# OPLink_Mini.net
KiCad netlist of a schematic drawn in Altium Designer
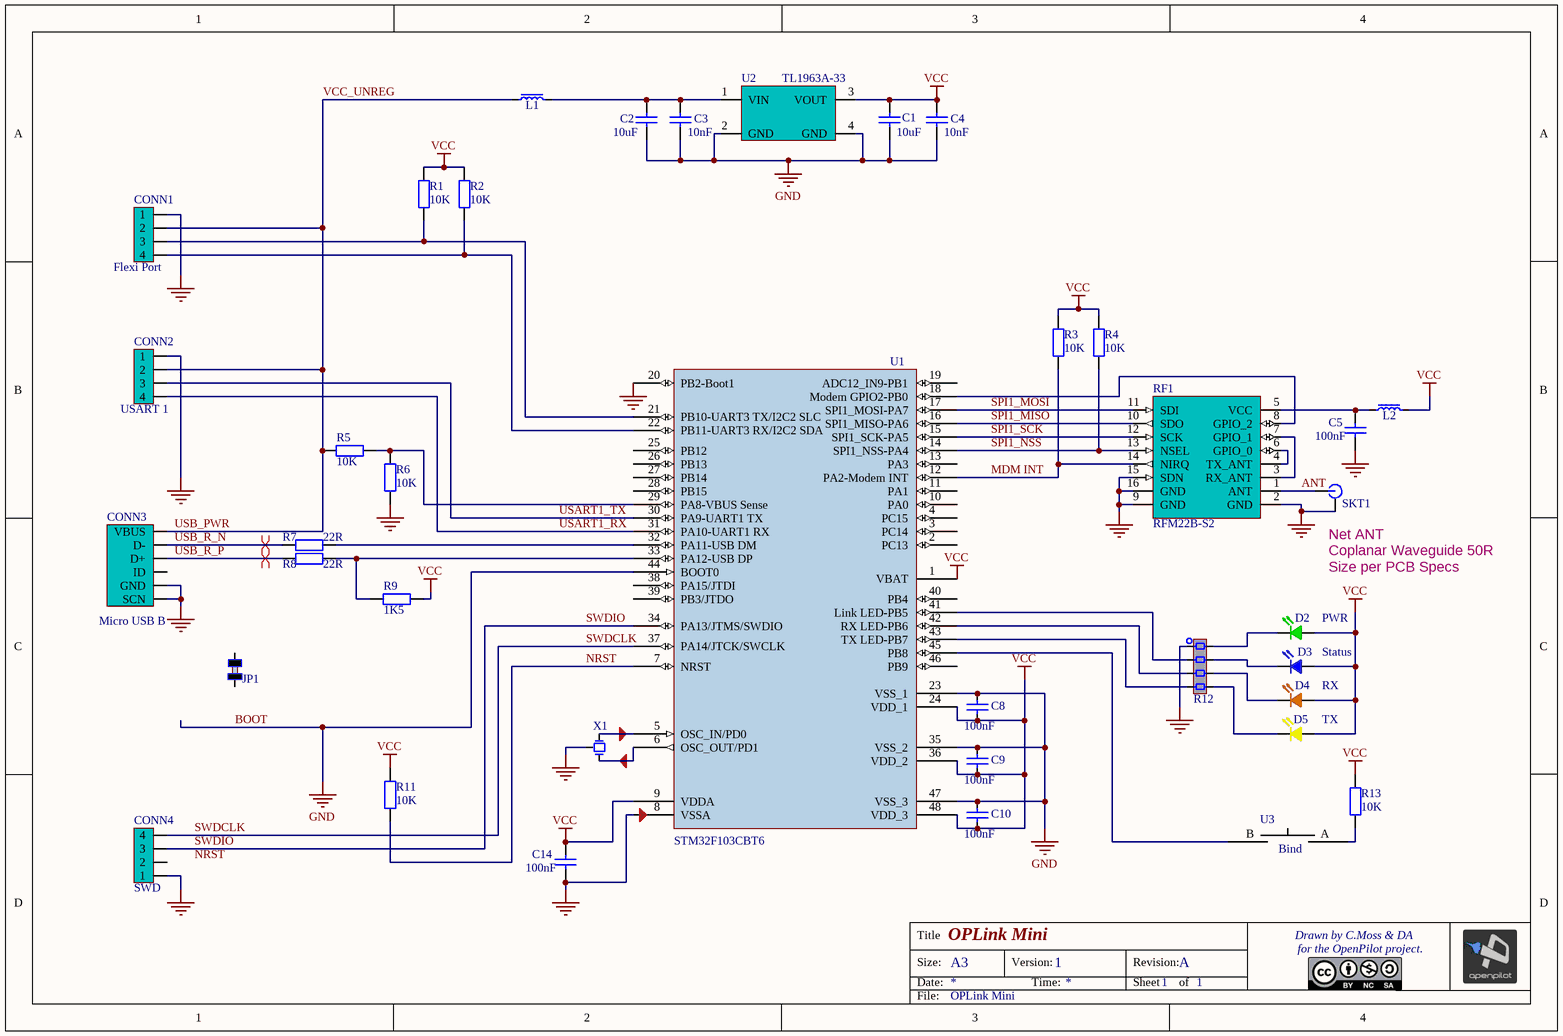
[diagram p0: OPLink Mini.SchDoc]

(export (version "E")
  (design (tool "Eeschema 10.0.6"))
  (components
    (comp (ref "C1")
      (value "10uF")
      (footprint "CAP805L")
      (description "Capacitor SMD")
      (fields (field (name "Comment") "Cap805") (field (name "PUBLISHER") "The OpenPilot Project"))
      (libsource (lib "OpenPilot") (part "Cap805"))
    )
    (comp (ref "C2")
      (value "10uF")
      (footprint "CAP805L")
      (description "Capacitor SMD")
      (fields (field (name "Comment") "Cap805") (field (name "PUBLISHER") "The OpenPilot Project"))
      (libsource (lib "OpenPilot") (part "Cap805"))
    )
    (comp (ref "C3")
      (value "10nF")
      (footprint "CAP402N")
      (description "Capacitor SMD")
      (fields (field (name "Comment") "10n") (field (name "PUBLISHER") "The OpenPilot Project"))
      (libsource (lib "OpenPilot") (part "Cap402"))
    )
    (comp (ref "C4")
      (value "10nF")
      (footprint "CAP402N")
      (description "Capacitor SMD")
      (fields (field (name "Comment") "10n") (field (name "PUBLISHER") "The OpenPilot Project"))
      (libsource (lib "OpenPilot") (part "Cap402"))
    )
    (comp (ref "C5")
      (value "100nF")
      (footprint "CAP402N")
      (description "Capacitor SMD")
      (fields (field (name "Comment") "Cap402") (field (name "PUBLISHER") "The OpenPilot Project"))
      (libsource (lib "OpenPilot") (part "Cap402"))
    )
    (comp (ref "C8")
      (value "100nF")
      (footprint "CAP402N")
      (description "Capacitor SMD")
      (fields (field (name "Comment") "Cap402") (field (name "PUBLISHER") "The OpenPilot Project"))
      (libsource (lib "") (part "Cap402_1"))
    )
    (comp (ref "C9")
      (value "100nF")
      (footprint "CAP402N")
      (description "Capacitor SMD")
      (fields (field (name "Comment") "Cap402") (field (name "PUBLISHER") "The OpenPilot Project"))
      (libsource (lib "") (part "Cap402_1"))
    )
    (comp (ref "C10")
      (value "100nF")
      (footprint "CAP402N")
      (description "Capacitor SMD")
      (fields (field (name "Comment") "Cap402") (field (name "PUBLISHER") "The OpenPilot Project"))
      (libsource (lib "") (part "Cap402_1"))
    )
    (comp (ref "C14")
      (value "100nF")
      (footprint "CAP402N")
      (description "Capacitor SMD")
      (fields (field (name "Comment") "Cap402") (field (name "PUBLISHER") "The OpenPilot Project"))
      (libsource (lib "OpenPilot") (part "Cap402"))
    )
    (comp (ref "CONN1")
      (value "Flexi Port")
      (footprint "JST SH 4 Pin Side Entry")
      (description "JST-SH 4-pin Side Entry Socket")
      (fields (field (name "MANUFACTURER") "Generic Components"))
      (libsource (lib "OpenPilot") (part "JST-SH 4-pin Side Entry Socket"))
    )
    (comp (ref "CONN2")
      (value "USART 1")
      (footprint "JST SH 4 Pin Side Entry")
      (description "JST-SH 4-pin Side Entry Socket")
      (fields (field (name "MANUFACTURER") "Generic Components"))
      (libsource (lib "OpenPilot") (part "JST-SH 4-pin Side Entry Socket"))
    )
    (comp (ref "CONN3")
      (value "Micro USB B")
      (footprint "Micro_USB")
      (description "USB Micro B SMT Socket")
      (fields (field (name "PUBLISHER") "The OpenPilot Project"))
      (libsource (lib "OpenPilot") (part "USB Micro B SMT"))
    )
    (comp (ref "CONN4")
      (value "SWD")
      (footprint "JST SH 4 Pin Side Entry")
      (description "JST-SH 4-pin Side Entry Socket")
      (fields (field (name "MANUFACTURER") "Generic Components"))
      (libsource (lib "") (part "JST-SH 4-pin Side Entry Socket_1"))
    )
    (comp (ref "D2")
      (value "PWR")
      (footprint "LED603N")
      (description "Green 603 LED")
      (libsource (lib "OpenPilot") (part "LED 603 Gr"))
    )
    (comp (ref "D3")
      (value "Status")
      (footprint "LED603N")
      (description "Blue 603 LED")
      (libsource (lib "OpenPilot") (part "LED 603 Bl"))
    )
    (comp (ref "D4")
      (value "RX")
      (footprint "LED603N")
      (description "Orange 603 LED")
      (libsource (lib "OpenPilot") (part "LED 603 Or"))
    )
    (comp (ref "D5")
      (value "TX")
      (footprint "LED603N")
      (description "Yellow 603 LED")
      (fields (field (name "PUBLISHER") "The OpenPilot Project"))
      (libsource (lib "OpenPilot") (part "LED 603 Yellow"))
    )
    (comp (ref "JP1")
      (value "2 PAD Touch JMP")
      (footprint "TOUCH JMP 2PAD")
      (description "2 Pad Touch Jumper")
      (fields (field (name "PUBLISHER") "The OpenPilot Project"))
      (libsource (lib "OpenPilot") (part "2 PAD Touch JMP"))
    )
    (comp (ref "L1")
      (value "300mA")
      (footprint "IND603N")
      (description "Ferrite Bead 300mA")
      (fields (field (name "MANUFACTURER") "Generic Components"))
      (libsource (lib "OpenPilot") (part "FerriteBead_300mA"))
    )
    (comp (ref "L2")
      (value "300mA")
      (footprint "IND603N")
      (description "Ferrite Bead 300mA")
      (fields (field (name "MANUFACTURER") "Generic Components"))
      (libsource (lib "OpenPilot") (part "FerriteBead_300mA"))
    )
    (comp (ref "R1")
      (value "10K")
      (footprint "RES402N")
      (description "Resistor SMD")
      (fields (field (name "Comment") "Res402") (field (name "PUBLISHER") "The OpenPilot Project"))
      (libsource (lib "") (part "Res402_2"))
    )
    (comp (ref "R2")
      (value "10K")
      (footprint "RES402N")
      (description "Resistor SMD")
      (fields (field (name "Comment") "Res402") (field (name "PUBLISHER") "The OpenPilot Project"))
      (libsource (lib "") (part "Res402_2"))
    )
    (comp (ref "R3")
      (value "10K")
      (footprint "RES402N")
      (description "Resistor SMD")
      (fields (field (name "Comment") "Res402") (field (name "PUBLISHER") "The OpenPilot Project"))
      (libsource (lib "") (part "Res402_2"))
    )
    (comp (ref "R4")
      (value "10K")
      (footprint "RES402N")
      (description "Resistor SMD")
      (fields (field (name "Comment") "Res402") (field (name "PUBLISHER") "The OpenPilot Project"))
      (libsource (lib "") (part "Res402_2"))
    )
    (comp (ref "R5")
      (value "10K")
      (footprint "RES402N")
      (description "Resistor SMD")
      (fields (field (name "Comment") "Res402") (field (name "PUBLISHER") "The OpenPilot Project"))
      (libsource (lib "") (part "Res402_1"))
    )
    (comp (ref "R6")
      (value "10K")
      (footprint "RES402N")
      (description "Resistor SMD")
      (fields (field (name "Comment") "Res402") (field (name "PUBLISHER") "The OpenPilot Project"))
      (libsource (lib "") (part "Res402_2"))
    )
    (comp (ref "R7")
      (value "22R")
      (footprint "RES402N")
      (description "Resistor SMD")
      (fields (field (name "Comment") "Res402") (field (name "PUBLISHER") "The OpenPilot Project"))
      (libsource (lib "") (part "Res402_1"))
    )
    (comp (ref "R8")
      (value "22R")
      (footprint "RES402N")
      (description "Resistor SMD")
      (fields (field (name "Comment") "Res402") (field (name "PUBLISHER") "The OpenPilot Project"))
      (libsource (lib "") (part "Res402_1"))
    )
    (comp (ref "R9")
      (value "1K5")
      (footprint "RES402N")
      (description "Resistor SMD")
      (fields (field (name "Comment") "Res402") (field (name "PUBLISHER") "The OpenPilot Project"))
      (libsource (lib "") (part "Res402_3"))
    )
    (comp (ref "R11")
      (value "10K")
      (footprint "RES402N")
      (description "Resistor SMD")
      (fields (field (name "Comment") "Res402") (field (name "PUBLISHER") "The OpenPilot Project"))
      (libsource (lib "OpenPilot") (part "Res402"))
    )
    (comp (ref "R12")
      (value "Res Array 330R 1206")
      (footprint "TC164")
      (description "4 Resistor Array")
      (fields (field (name "PUBLISHER") "The OpenPilot Project"))
      (libsource (lib "OpenPilot") (part "Res Array 330R"))
    )
    (comp (ref "R13")
      (value "10K")
      (footprint "RES402N")
      (description "Resistor SMD")
      (fields (field (name "Comment") "Res402") (field (name "PUBLISHER") "The OpenPilot Project"))
      (libsource (lib "OpenPilot") (part "Res402"))
    )
    (comp (ref "RF1")
      (value "RFM22B-S2")
      (footprint "RFM22-S2")
      (description "UHF 100mW Transceiver")
      (libsource (lib "OpenPilot") (part "RFM22B-S2"))
    )
    (comp (ref "SKT1")
      (value "MMCX Thru hole")
      (footprint "MMCX_SOCKET")
      (description "MMCX Socket")
      (libsource (lib "OpenPilot") (part "MMCX Thru hole"))
    )
    (comp (ref "U1")
      (value "STM32F103CBT6")
      (footprint "STM32 48 Lead")
      (description "STM32 ARM-based 32-bit MCU with 128 Kbytes Flash, 48-pin LQFP, Industrial Temperature")
      (fields (field (name "PUBLISHER") "Altium Limited"))
      (libsource (lib "OpenPilot") (part "STM32F103CBT6"))
    )
    (comp (ref "U2")
      (value "TL1963A-33")
      (footprint "SOT223")
      (description "3.3V 1.5A LDO Regulator")
      (fields (field (name "PUBLISHER") "The OpenPilot Project"))
      (libsource (lib "OpenPilot") (part "TL1963A-33"))
    )
    (comp (ref "U3")
      (value "Bind")
      (footprint "B3U-1000P")
      (description "Push Button SMD")
      (libsource (lib "OpenPilot") (part "Push Switch Small"))
    )
    (comp (ref "X1")
      (value "8Mhz Ceralock")
      (footprint "CERALOCK 8Mhz")
      (description "Ceralock 8Mhz with caps")
      (fields (field (name "PUBLISHER") "The OpenPilot Project"))
      (libsource (lib "OpenPilot") (part "CERALOCK8"))
    )
  )
  (nets
    (net (code "1") (name "/ANT") (class "Default")
      (node (ref "RF1") (pin "1") (pinfunction "ANT_1") (pintype "passive"))
      (node (ref "SKT1") (pin "1") (pinfunction "PIN_1") (pintype "passive"))
    )
    (net (code "2") (name "/MDM INT") (class "Default")
      (node (ref "R3") (pin "2") (pinfunction "2_2") (pintype "passive"))
      (node (ref "RF1") (pin "14") (pinfunction "NIRQ_14") (pintype "output"))
      (node (ref "U1") (pin "12") (pinfunction "PA2-Modem_INT_12") (pintype "bidirectional"))
    )
    (net (code "3") (name "/NRST") (class "Default")
      (node (ref "R11") (pin "1") (pinfunction "1_1") (pintype "passive"))
      (node (ref "U1") (pin "7") (pinfunction "NRST_7") (pintype "bidirectional"))
    )
    (net (code "4") (name "/SPI1_MISO") (class "Default")
      (node (ref "RF1") (pin "10") (pinfunction "SDO_10") (pintype "output"))
      (node (ref "U1") (pin "16") (pinfunction "SPI1_MISO-PA6_16") (pintype "bidirectional"))
    )
    (net (code "5") (name "/SPI1_MOSI") (class "Default")
      (node (ref "RF1") (pin "11") (pinfunction "SDI_11") (pintype "input"))
      (node (ref "U1") (pin "17") (pinfunction "SPI1_MOSI-PA7_17") (pintype "bidirectional"))
    )
    (net (code "6") (name "/SPI1_NSS") (class "Default")
      (node (ref "R4") (pin "2") (pinfunction "2_2") (pintype "passive"))
      (node (ref "RF1") (pin "13") (pinfunction "NSEL_13") (pintype "input"))
      (node (ref "U1") (pin "14") (pinfunction "SPI1_NSS-PA4_14") (pintype "bidirectional"))
    )
    (net (code "7") (name "/SPI1_SCK") (class "Default")
      (node (ref "RF1") (pin "12") (pinfunction "SCK_12") (pintype "input"))
      (node (ref "U1") (pin "15") (pinfunction "SPI1_SCK-PA5_15") (pintype "bidirectional"))
    )
    (net (code "8") (name "/SWDCLK") (class "Default")
      (node (ref "CONN4") (pin "4") (pinfunction "4_4") (pintype "passive"))
      (node (ref "U1") (pin "37") (pinfunction "PA14/JTCK/SWCLK_37") (pintype "bidirectional"))
    )
    (net (code "9") (name "/SWDIO") (class "Default")
      (node (ref "CONN4") (pin "3") (pinfunction "3_3") (pintype "passive"))
      (node (ref "U1") (pin "34") (pinfunction "PA13/JTMS/SWDIO_34") (pintype "bidirectional"))
    )
    (net (code "10") (name "/USART1_RX") (class "Default")
      (node (ref "CONN2") (pin "4") (pinfunction "4_4") (pintype "passive"))
      (node (ref "U1") (pin "31") (pinfunction "PA10-UART1_RX_31") (pintype "bidirectional"))
    )
    (net (code "11") (name "/USART1_TX") (class "Default")
      (node (ref "CONN2") (pin "3") (pinfunction "3_3") (pintype "passive"))
      (node (ref "U1") (pin "30") (pinfunction "PA9-UART1_TX_30") (pintype "bidirectional"))
    )
    (net (code "12") (name "/USB_PWR") (class "Default")
      (node (ref "CONN1") (pin "2") (pinfunction "2_2") (pintype "passive"))
      (node (ref "CONN2") (pin "2") (pinfunction "2_2") (pintype "passive"))
      (node (ref "CONN3") (pin "1") (pinfunction "VBUS_1") (pintype "passive"))
      (node (ref "L1") (pin "2") (pinfunction "2_2") (pintype "passive"))
      (node (ref "R5") (pin "2") (pinfunction "2_2") (pintype "passive"))
    )
    (net (code "13") (name "/USB_R_N") (class "Default")
      (node (ref "CONN3") (pin "2") (pinfunction "D-_2") (pintype "passive"))
      (node (ref "R7") (pin "2") (pinfunction "2_2") (pintype "passive"))
    )
    (net (code "14") (name "/USB_R_P") (class "Default")
      (node (ref "CONN3") (pin "3") (pinfunction "D+_3") (pintype "passive"))
      (node (ref "R8") (pin "2") (pinfunction "2_2") (pintype "passive"))
    )
    (net (code "15") (name "GND") (class "Default")
      (node (ref "C1") (pin "2") (pinfunction "2_2") (pintype "passive"))
      (node (ref "C10") (pin "1") (pinfunction "1_1") (pintype "passive"))
      (node (ref "C14") (pin "2") (pinfunction "2_2") (pintype "passive"))
      (node (ref "C2") (pin "2") (pinfunction "2_2") (pintype "passive"))
      (node (ref "C3") (pin "2") (pinfunction "2_2") (pintype "passive"))
      (node (ref "C4") (pin "2") (pinfunction "2_2") (pintype "passive"))
      (node (ref "C5") (pin "2") (pinfunction "2_2") (pintype "passive"))
      (node (ref "C8") (pin "1") (pinfunction "1_1") (pintype "passive"))
      (node (ref "C9") (pin "1") (pinfunction "1_1") (pintype "passive"))
      (node (ref "CONN1") (pin "1") (pinfunction "1_1") (pintype "passive"))
      (node (ref "CONN2") (pin "1") (pinfunction "1_1") (pintype "passive"))
      (node (ref "CONN3") (pin "0") (pinfunction "SCN_0") (pintype "passive"))
      (node (ref "CONN3") (pin "5") (pinfunction "GND_5") (pintype "passive"))
      (node (ref "CONN4") (pin "1") (pinfunction "1_1") (pintype "passive"))
      (node (ref "R12") (pin "1") (pinfunction "1_1") (pintype "passive"))
      (node (ref "R6") (pin "2") (pinfunction "2_2") (pintype "passive"))
      (node (ref "RF1") (pin "15") (pinfunction "SDN_15") (pintype "input"))
      (node (ref "RF1") (pin "16") (pinfunction "GND_16") (pintype "power_in"))
      (node (ref "RF1") (pin "2") (pinfunction "GND_2") (pintype "power_in"))
      (node (ref "RF1") (pin "9") (pinfunction "GND_9") (pintype "power_in"))
      (node (ref "SKT1") (pin "2") (pinfunction "GND_2") (pintype "passive"))
      (node (ref "U1") (pin "20") (pinfunction "PB2-Boot1_20") (pintype "bidirectional"))
      (node (ref "U1") (pin "23") (pinfunction "VSS_1_23") (pintype "power_in"))
      (node (ref "U1") (pin "35") (pinfunction "VSS_2_35") (pintype "power_in"))
      (node (ref "U1") (pin "44") (pinfunction "BOOT0_44") (pintype "input"))
      (node (ref "U1") (pin "47") (pinfunction "VSS_3_47") (pintype "power_in"))
      (node (ref "U1") (pin "8") (pinfunction "VSSA_8") (pintype "power_in"))
      (node (ref "U2") (pin "2") (pinfunction "GND_2") (pintype "power_in"))
      (node (ref "U2") (pin "4") (pinfunction "GND_4") (pintype "power_in"))
      (node (ref "X1") (pin "3") (pinfunction "3_3") (pintype "passive"))
    )
    (net (code "16") (name "Net-(D2-K)") (class "Default")
      (node (ref "D2") (pin "1") (pinfunction "K_1") (pintype "passive"))
      (node (ref "R12") (pin "8") (pinfunction "8_8") (pintype "passive"))
    )
    (net (code "17") (name "Net-(D3-K)") (class "Default")
      (node (ref "D3") (pin "1") (pinfunction "K_1") (pintype "passive"))
      (node (ref "R12") (pin "7") (pinfunction "7_7") (pintype "passive"))
    )
    (net (code "18") (name "Net-(D4-K)") (class "Default")
      (node (ref "D4") (pin "1") (pinfunction "K_1") (pintype "passive"))
      (node (ref "R12") (pin "6") (pinfunction "6_6") (pintype "passive"))
    )
    (net (code "19") (name "Net-(D5-K)") (class "Default")
      (node (ref "D5") (pin "1") (pinfunction "K_1") (pintype "passive"))
      (node (ref "R12") (pin "5") (pinfunction "5_5") (pintype "passive"))
    )
    (net (code "20") (name "Net-(R13-Pad1)") (class "Default")
      (node (ref "R13") (pin "1") (pinfunction "1_1") (pintype "passive"))
      (node (ref "U3") (pin "A") (pinfunction "A_A") (pintype "power_in"))
    )
    (net (code "21") (name "Net-(RF1-GPIO_0)") (class "Default")
      (node (ref "RF1") (pin "4") (pinfunction "TX_ANT_4") (pintype "passive"))
      (node (ref "RF1") (pin "6") (pinfunction "GPIO_0_6") (pintype "bidirectional"))
    )
    (net (code "22") (name "Net-(RF1-GPIO_1)") (class "Default")
      (node (ref "RF1") (pin "3") (pinfunction "RX_ANT_3") (pintype "passive"))
      (node (ref "RF1") (pin "7") (pinfunction "GPIO_1_7") (pintype "bidirectional"))
    )
    (net (code "23") (name "Net-(RF1-GPIO_2)") (class "Default")
      (node (ref "RF1") (pin "8") (pinfunction "GPIO_2_8") (pintype "bidirectional"))
      (node (ref "U1") (pin "18") (pinfunction "Modem_GPIO2-PB0_18") (pintype "bidirectional"))
    )
    (net (code "24") (name "Net-(RF1-VCC)") (class "Default")
      (node (ref "C5") (pin "1") (pinfunction "1_1") (pintype "passive"))
      (node (ref "L2") (pin "2") (pinfunction "2_2") (pintype "passive"))
      (node (ref "RF1") (pin "5") (pinfunction "VCC_5") (pintype "power_in"))
    )
    (net (code "25") (name "Net-(U1-Link_LED-PB5)") (class "Default")
      (node (ref "R12") (pin "2") (pinfunction "2_2") (pintype "passive"))
      (node (ref "U1") (pin "41") (pinfunction "Link_LED-PB5_41") (pintype "bidirectional"))
    )
    (net (code "26") (name "Net-(U1-OSC_IN{slash}PD0)") (class "Default")
      (node (ref "U1") (pin "5") (pinfunction "OSC_IN/PD0_5") (pintype "input"))
      (node (ref "X1") (pin "1") (pinfunction "1_1") (pintype "passive"))
    )
    (net (code "27") (name "Net-(U1-OSC_OUT{slash}PD1)") (class "Default")
      (node (ref "U1") (pin "6") (pinfunction "OSC_OUT/PD1_6") (pintype "output"))
      (node (ref "X1") (pin "2") (pinfunction "2_2") (pintype "passive"))
    )
    (net (code "28") (name "Net-(U1-PA8-VBUS_Sense)") (class "Default")
      (node (ref "R5") (pin "1") (pinfunction "1_1") (pintype "passive"))
      (node (ref "R6") (pin "1") (pinfunction "1_1") (pintype "passive"))
      (node (ref "U1") (pin "29") (pinfunction "PA8-VBUS_Sense_29") (pintype "bidirectional"))
    )
    (net (code "29") (name "Net-(U1-PA11-USB_DM)") (class "Default")
      (node (ref "R7") (pin "1") (pinfunction "1_1") (pintype "passive"))
      (node (ref "U1") (pin "32") (pinfunction "PA11-USB_DM_32") (pintype "bidirectional"))
    )
    (net (code "30") (name "Net-(U1-PA12-USB_DP)") (class "Default")
      (node (ref "R8") (pin "1") (pinfunction "1_1") (pintype "passive"))
      (node (ref "R9") (pin "1") (pinfunction "1_1") (pintype "passive"))
      (node (ref "U1") (pin "33") (pinfunction "PA12-USB_DP_33") (pintype "bidirectional"))
    )
    (net (code "31") (name "Net-(U1-PB8)") (class "Default")
      (node (ref "U1") (pin "45") (pinfunction "PB8_45") (pintype "bidirectional"))
      (node (ref "U3") (pin "B") (pinfunction "B_B") (pintype "power_in"))
    )
    (net (code "32") (name "Net-(U1-PB10-UART3_TX{slash}I2C2_SLC)") (class "Default")
      (node (ref "CONN1") (pin "3") (pinfunction "3_3") (pintype "passive"))
      (node (ref "R1") (pin "2") (pinfunction "2_2") (pintype "passive"))
      (node (ref "U1") (pin "21") (pinfunction "PB10-UART3_TX/I2C2_SLC_21") (pintype "bidirectional"))
    )
    (net (code "33") (name "Net-(U1-PB11-UART3_RX{slash}I2C2_SDA)") (class "Default")
      (node (ref "CONN1") (pin "4") (pinfunction "4_4") (pintype "passive"))
      (node (ref "R2") (pin "2") (pinfunction "2_2") (pintype "passive"))
      (node (ref "U1") (pin "22") (pinfunction "PB11-UART3_RX/I2C2_SDA_22") (pintype "bidirectional"))
    )
    (net (code "34") (name "Net-(U1-RX_LED-PB6)") (class "Default")
      (node (ref "R12") (pin "3") (pinfunction "3_3") (pintype "passive"))
      (node (ref "U1") (pin "42") (pinfunction "RX_LED-PB6_42") (pintype "bidirectional"))
    )
    (net (code "35") (name "Net-(U1-TX_LED-PB7)") (class "Default")
      (node (ref "R12") (pin "4") (pinfunction "4_4") (pintype "passive"))
      (node (ref "U1") (pin "43") (pinfunction "TX_LED-PB7_43") (pintype "bidirectional"))
    )
    (net (code "36") (name "Net-(U2-VIN)") (class "Default")
      (node (ref "C2") (pin "1") (pinfunction "1_1") (pintype "passive"))
      (node (ref "C3") (pin "1") (pinfunction "1_1") (pintype "passive"))
      (node (ref "L1") (pin "1") (pinfunction "1_1") (pintype "passive"))
      (node (ref "U2") (pin "1") (pinfunction "VIN_1") (pintype "power_in"))
    )
    (net (code "37") (name "VCC") (class "Default")
      (node (ref "C1") (pin "1") (pinfunction "1_1") (pintype "passive"))
      (node (ref "C10") (pin "2") (pinfunction "2_2") (pintype "passive"))
      (node (ref "C14") (pin "1") (pinfunction "1_1") (pintype "passive"))
      (node (ref "C4") (pin "1") (pinfunction "1_1") (pintype "passive"))
      (node (ref "C8") (pin "2") (pinfunction "2_2") (pintype "passive"))
      (node (ref "C9") (pin "2") (pinfunction "2_2") (pintype "passive"))
      (node (ref "D2") (pin "2") (pinfunction "A_2") (pintype "passive"))
      (node (ref "D3") (pin "2") (pinfunction "A_2") (pintype "passive"))
      (node (ref "D4") (pin "2") (pinfunction "A_2") (pintype "passive"))
      (node (ref "D5") (pin "2") (pinfunction "A_2") (pintype "passive"))
      (node (ref "L2") (pin "1") (pinfunction "1_1") (pintype "passive"))
      (node (ref "R1") (pin "1") (pinfunction "1_1") (pintype "passive"))
      (node (ref "R11") (pin "2") (pinfunction "2_2") (pintype "passive"))
      (node (ref "R13") (pin "2") (pinfunction "2_2") (pintype "passive"))
      (node (ref "R2") (pin "1") (pinfunction "1_1") (pintype "passive"))
      (node (ref "R3") (pin "1") (pinfunction "1_1") (pintype "passive"))
      (node (ref "R4") (pin "1") (pinfunction "1_1") (pintype "passive"))
      (node (ref "R9") (pin "2") (pinfunction "2_2") (pintype "passive"))
      (node (ref "U1") (pin "1") (pinfunction "VBAT_1") (pintype "power_in"))
      (node (ref "U1") (pin "24") (pinfunction "VDD_1_24") (pintype "power_in"))
      (node (ref "U1") (pin "36") (pinfunction "VDD_2_36") (pintype "power_in"))
      (node (ref "U1") (pin "48") (pinfunction "VDD_3_48") (pintype "power_in"))
      (node (ref "U1") (pin "9") (pinfunction "VDDA_9") (pintype "power_in"))
      (node (ref "U2") (pin "3") (pinfunction "VOUT_3") (pintype "power_in"))
    )
    (net (code "38") (name "unconnected-(CONN3-ID-Pad4)") (class "Default")
      (node (ref "CONN3") (pin "4") (pinfunction "ID_4") (pintype "passive"))
    )
    (net (code "39") (name "unconnected-(CONN4-Pad2)") (class "Default")
      (node (ref "CONN4") (pin "2") (pinfunction "2_2") (pintype "passive"))
    )
    (net (code "40") (name "unconnected-(JP1-Pad1)") (class "Default")
      (node (ref "JP1") (pin "1") (pinfunction "1_1") (pintype "passive"))
    )
    (net (code "41") (name "unconnected-(JP1-Pad2)") (class "Default")
      (node (ref "JP1") (pin "2") (pinfunction "2_2") (pintype "passive"))
    )
    (net (code "42") (name "unconnected-(RF1-N.C-Pad1)") (class "Default")
      (node (ref "RF1") (pin "1") (pinfunction "N.C_1") (pintype "tri_state"))
    )
    (net (code "43") (name "unconnected-(RF1-N.C-Pad4)") (class "Default")
      (node (ref "RF1") (pin "4") (pinfunction "N.C_4") (pintype "tri_state"))
    )
    (net (code "44") (name "unconnected-(RF1-N.C-Pad8)") (class "Default")
      (node (ref "RF1") (pin "8") (pinfunction "N.C_8") (pintype "tri_state"))
    )
    (net (code "45") (name "unconnected-(RF1-N.C-Pad9)") (class "Default")
      (node (ref "RF1") (pin "9") (pinfunction "N.C_9") (pintype "tri_state"))
    )
    (net (code "46") (name "unconnected-(RF1-N.C-Pad14)") (class "Default")
      (node (ref "RF1") (pin "14") (pinfunction "N.C_14") (pintype "tri_state"))
    )
    (net (code "47") (name "unconnected-(U1-ADC12_IN9-PB1-Pad19)") (class "Default")
      (node (ref "U1") (pin "19") (pinfunction "ADC12_IN9-PB1_19") (pintype "bidirectional"))
    )
    (net (code "48") (name "unconnected-(U1-PA0-Pad10)") (class "Default")
      (node (ref "U1") (pin "10") (pinfunction "PA0_10") (pintype "bidirectional"))
    )
    (net (code "49") (name "unconnected-(U1-PA1-Pad11)") (class "Default")
      (node (ref "U1") (pin "11") (pinfunction "PA1_11") (pintype "bidirectional"))
    )
    (net (code "50") (name "unconnected-(U1-PA3-Pad13)") (class "Default")
      (node (ref "U1") (pin "13") (pinfunction "PA3_13") (pintype "bidirectional"))
    )
    (net (code "51") (name "unconnected-(U1-PA15{slash}JTDI-Pad38)") (class "Default")
      (node (ref "U1") (pin "38") (pinfunction "PA15/JTDI_38") (pintype "bidirectional"))
    )
    (net (code "52") (name "unconnected-(U1-PB3{slash}JTDO-Pad39)") (class "Default")
      (node (ref "U1") (pin "39") (pinfunction "PB3/JTDO_39") (pintype "bidirectional"))
    )
    (net (code "53") (name "unconnected-(U1-PB4-Pad40)") (class "Default")
      (node (ref "U1") (pin "40") (pinfunction "PB4_40") (pintype "bidirectional"))
    )
    (net (code "54") (name "unconnected-(U1-PB9-Pad46)") (class "Default")
      (node (ref "U1") (pin "46") (pinfunction "PB9_46") (pintype "bidirectional"))
    )
    (net (code "55") (name "unconnected-(U1-PB12-Pad25)") (class "Default")
      (node (ref "U1") (pin "25") (pinfunction "PB12_25") (pintype "bidirectional"))
    )
    (net (code "56") (name "unconnected-(U1-PB13-Pad26)") (class "Default")
      (node (ref "U1") (pin "26") (pinfunction "PB13_26") (pintype "bidirectional"))
    )
    (net (code "57") (name "unconnected-(U1-PB14-Pad27)") (class "Default")
      (node (ref "U1") (pin "27") (pinfunction "PB14_27") (pintype "bidirectional"))
    )
    (net (code "58") (name "unconnected-(U1-PB15-Pad28)") (class "Default")
      (node (ref "U1") (pin "28") (pinfunction "PB15_28") (pintype "bidirectional"))
    )
    (net (code "59") (name "unconnected-(U1-PC13-Pad2)") (class "Default")
      (node (ref "U1") (pin "2") (pinfunction "PC13_2") (pintype "bidirectional"))
    )
    (net (code "60") (name "unconnected-(U1-PC14-Pad3)") (class "Default")
      (node (ref "U1") (pin "3") (pinfunction "PC14_3") (pintype "bidirectional"))
    )
    (net (code "61") (name "unconnected-(U1-PC15-Pad4)") (class "Default")
      (node (ref "U1") (pin "4") (pinfunction "PC15_4") (pintype "bidirectional"))
    )
  )
)
